# Sheet_1_3OLED.net
KiCad netlist of a schematic drawn in Altium Designer
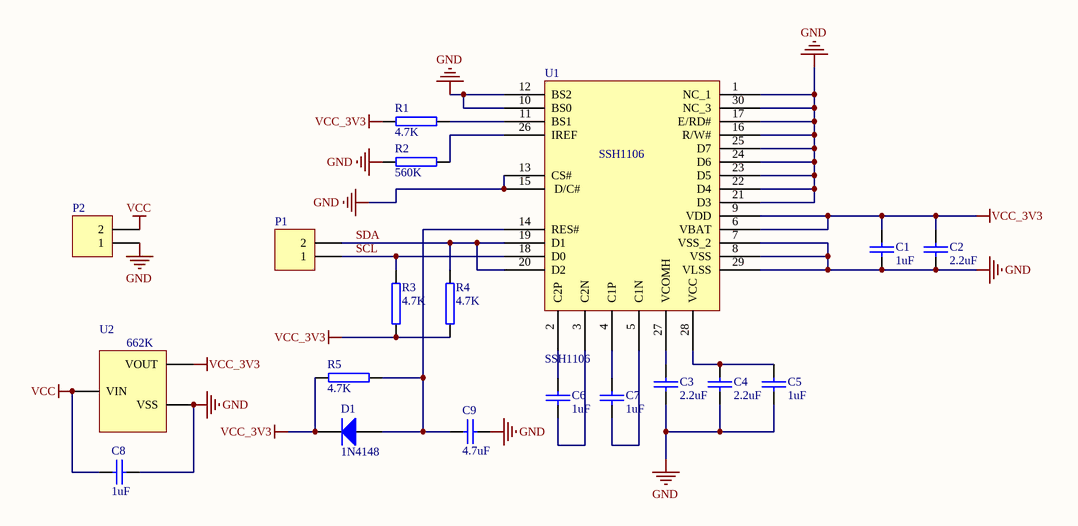
[diagram p0: Sheet_1.3OLED.SchDoc]

(export (version "E")
  (design (tool "Eeschema 10.0.6"))
  (components
    (comp (ref "C1")
      (value "1uF")
      (footprint "C0603")
      (description "贴片电容")
      (libsource (lib "Schlib_OLEDMCU") (part "C0603"))
    )
    (comp (ref "C2")
      (value "2.2uF")
      (footprint "C0603")
      (description "贴片电容")
      (libsource (lib "Schlib_OLEDMCU") (part "C0603"))
    )
    (comp (ref "C3")
      (value "2.2uF")
      (footprint "C0603")
      (description "贴片电容")
      (libsource (lib "Schlib_OLEDMCU") (part "C0603"))
    )
    (comp (ref "C4")
      (value "2.2uF")
      (footprint "C0603")
      (description "贴片电容")
      (libsource (lib "Schlib_OLEDMCU") (part "C0603"))
    )
    (comp (ref "C5")
      (value "1uF")
      (footprint "C0603")
      (description "贴片电容")
      (libsource (lib "Schlib_OLEDMCU") (part "C0603"))
    )
    (comp (ref "C6")
      (value "1uF")
      (footprint "C0603")
      (description "贴片电容")
      (libsource (lib "Schlib_OLEDMCU") (part "C0603"))
    )
    (comp (ref "C7")
      (value "1uF")
      (footprint "C0603")
      (description "贴片电容")
      (libsource (lib "Schlib_OLEDMCU") (part "C0603"))
    )
    (comp (ref "C8")
      (value "1uF")
      (footprint "C0603")
      (description "贴片电容")
      (libsource (lib "Schlib_OLEDMCU") (part "C0603"))
    )
    (comp (ref "C9")
      (value "4.7uF")
      (footprint "C0603")
      (description "贴片电容")
      (libsource (lib "Schlib_OLEDMCU") (part "C0603"))
    )
    (comp (ref "D1")
      (value "1N4148")
      (footprint "1n4148")
      (description "二极管")
      (libsource (lib "Schlib_OLEDMCU") (part "1N4148"))
    )
    (comp (ref "P1")
      (value "Header 2")
      (footprint "HDR1X2")
      (description "Header, 2-Pin")
      (fields (field (name "PUBLISHER") "Altium Limited"))
      (libsource (lib "Miscellaneous Connectors") (part "Header 2"))
    )
    (comp (ref "P2")
      (value "Header 2")
      (footprint "HDR1X2")
      (description "Header, 2-Pin")
      (fields (field (name "PUBLISHER") "Altium Limited"))
      (libsource (lib "Miscellaneous Connectors") (part "Header 2"))
    )
    (comp (ref "R1")
      (value "4.7K")
      (footprint "R0603")
      (description "贴片电阻")
      (libsource (lib "Schlib_OLEDMCU") (part "R0603"))
    )
    (comp (ref "R2")
      (value "560K")
      (footprint "R0603")
      (description "贴片电阻")
      (libsource (lib "Schlib_OLEDMCU") (part "R0603"))
    )
    (comp (ref "R3")
      (value "4.7K")
      (footprint "R0603")
      (description "贴片电阻")
      (libsource (lib "Schlib_OLEDMCU") (part "R0603"))
    )
    (comp (ref "R4")
      (value "4.7K")
      (footprint "R0603")
      (description "贴片电阻")
      (libsource (lib "Schlib_OLEDMCU") (part "R0603"))
    )
    (comp (ref "R5")
      (value "4.7K")
      (footprint "R0603")
      (description "贴片电阻")
      (libsource (lib "Schlib_OLEDMCU") (part "R0603"))
    )
    (comp (ref "U1")
      (value "SSH1106")
      (footprint "SSH1106")
      (description "1.3寸OLED")
      (libsource (lib "Schlib_OLEDMCU") (part "SSH1106"))
    )
    (comp (ref "U2")
      (value "Power")
      (footprint "662k")
      (description "稳压芯片")
      (libsource (lib "Schlib_OLEDMCU") (part "662K"))
    )
  )
  (nets
    (net (code "1") (name "/SCL") (class "Default")
      (node (ref "P1") (pin "1") (pinfunction "1_1") (pintype "passive"))
      (node (ref "R3") (pin "2") (pinfunction "2_2") (pintype "passive"))
      (node (ref "U1") (pin "18") (pinfunction "D0_18") (pintype "passive"))
    )
    (net (code "2") (name "/SDA") (class "Default")
      (node (ref "P1") (pin "2") (pinfunction "2_2") (pintype "passive"))
      (node (ref "R4") (pin "2") (pinfunction "2_2") (pintype "passive"))
      (node (ref "U1") (pin "19") (pinfunction "D1_19") (pintype "passive"))
      (node (ref "U1") (pin "20") (pinfunction "D2_20") (pintype "passive"))
    )
    (net (code "3") (name "GND") (class "Default")
      (node (ref "C1") (pin "2") (pinfunction "2_2") (pintype "passive"))
      (node (ref "C2") (pin "2") (pinfunction "2_2") (pintype "passive"))
      (node (ref "C3") (pin "2") (pinfunction "2_2") (pintype "passive"))
      (node (ref "C4") (pin "2") (pinfunction "2_2") (pintype "passive"))
      (node (ref "C5") (pin "2") (pinfunction "2_2") (pintype "passive"))
      (node (ref "C8") (pin "2") (pinfunction "2_2") (pintype "passive"))
      (node (ref "C9") (pin "2") (pinfunction "2_2") (pintype "passive"))
      (node (ref "P2") (pin "1") (pinfunction "1_1") (pintype "passive"))
      (node (ref "R2") (pin "1") (pinfunction "1_1") (pintype "passive"))
      (node (ref "U1") (pin "1") (pinfunction "NC_1_1") (pintype "passive"))
      (node (ref "U1") (pin "10") (pinfunction "BS0_10") (pintype "passive"))
      (node (ref "U1") (pin "12") (pinfunction "BS2_12") (pintype "passive"))
      (node (ref "U1") (pin "13") (pinfunction "CS#_13") (pintype "passive"))
      (node (ref "U1") (pin "15") (pinfunction "D/C#_15") (pintype "passive"))
      (node (ref "U1") (pin "16") (pinfunction "R/W#_16") (pintype "passive"))
      (node (ref "U1") (pin "17") (pinfunction "E/RD#_17") (pintype "passive"))
      (node (ref "U1") (pin "21") (pinfunction "D3_21") (pintype "passive"))
      (node (ref "U1") (pin "22") (pinfunction "D4_22") (pintype "passive"))
      (node (ref "U1") (pin "23") (pinfunction "D5_23") (pintype "passive"))
      (node (ref "U1") (pin "24") (pinfunction "D6_24") (pintype "passive"))
      (node (ref "U1") (pin "25") (pinfunction "D7_25") (pintype "passive"))
      (node (ref "U1") (pin "29") (pinfunction "VLSS_29") (pintype "passive"))
      (node (ref "U1") (pin "30") (pinfunction "NC_3_30") (pintype "passive"))
      (node (ref "U1") (pin "7") (pinfunction "VSS_2_7") (pintype "passive"))
      (node (ref "U1") (pin "8") (pinfunction "VSS_8") (pintype "passive"))
      (node (ref "U2") (pin "1") (pinfunction "VSS_1") (pintype "passive"))
    )
    (net (code "4") (name "Net-(D1-A)") (class "Default")
      (node (ref "C9") (pin "1") (pinfunction "1_1") (pintype "passive"))
      (node (ref "D1") (pin "1") (pinfunction "A_1") (pintype "passive"))
      (node (ref "R5") (pin "2") (pinfunction "2_2") (pintype "passive"))
      (node (ref "U1") (pin "14") (pinfunction "RES#_14") (pintype "passive"))
    )
    (net (code "5") (name "Net-(U1-BS1)") (class "Default")
      (node (ref "R1") (pin "2") (pinfunction "2_2") (pintype "passive"))
      (node (ref "U1") (pin "11") (pinfunction "BS1_11") (pintype "passive"))
    )
    (net (code "6") (name "Net-(U1-C1N)") (class "Default")
      (node (ref "C7") (pin "2") (pinfunction "2_2") (pintype "passive"))
      (node (ref "U1") (pin "5") (pinfunction "C1N_5") (pintype "passive"))
    )
    (net (code "7") (name "Net-(U1-C1P)") (class "Default")
      (node (ref "C7") (pin "1") (pinfunction "1_1") (pintype "passive"))
      (node (ref "U1") (pin "4") (pinfunction "C1P_4") (pintype "passive"))
    )
    (net (code "8") (name "Net-(U1-C2N)") (class "Default")
      (node (ref "C6") (pin "2") (pinfunction "2_2") (pintype "passive"))
      (node (ref "U1") (pin "3") (pinfunction "C2N_3") (pintype "passive"))
    )
    (net (code "9") (name "Net-(U1-C2P)") (class "Default")
      (node (ref "C6") (pin "1") (pinfunction "1_1") (pintype "passive"))
      (node (ref "U1") (pin "2") (pinfunction "C2P_2") (pintype "passive"))
    )
    (net (code "10") (name "Net-(U1-IREF)") (class "Default")
      (node (ref "R2") (pin "2") (pinfunction "2_2") (pintype "passive"))
      (node (ref "U1") (pin "26") (pinfunction "IREF_26") (pintype "passive"))
    )
    (net (code "11") (name "Net-(U1-VCC)") (class "Default")
      (node (ref "C4") (pin "1") (pinfunction "1_1") (pintype "passive"))
      (node (ref "C5") (pin "1") (pinfunction "1_1") (pintype "passive"))
      (node (ref "U1") (pin "28") (pinfunction "VCC_28") (pintype "passive"))
    )
    (net (code "12") (name "Net-(U1-VCOMH)") (class "Default")
      (node (ref "C3") (pin "1") (pinfunction "1_1") (pintype "passive"))
      (node (ref "U1") (pin "27") (pinfunction "VCOMH_27") (pintype "passive"))
    )
    (net (code "13") (name "VCC") (class "Default")
      (node (ref "C8") (pin "1") (pinfunction "1_1") (pintype "passive"))
      (node (ref "P2") (pin "2") (pinfunction "2_2") (pintype "passive"))
      (node (ref "U2") (pin "3") (pinfunction "VIN_3") (pintype "passive"))
    )
    (net (code "14") (name "VCC_3V3") (class "Default")
      (node (ref "C1") (pin "1") (pinfunction "1_1") (pintype "passive"))
      (node (ref "C2") (pin "1") (pinfunction "1_1") (pintype "passive"))
      (node (ref "D1") (pin "2") (pinfunction "K_2") (pintype "passive"))
      (node (ref "R1") (pin "1") (pinfunction "1_1") (pintype "passive"))
      (node (ref "R3") (pin "1") (pinfunction "1_1") (pintype "passive"))
      (node (ref "R4") (pin "1") (pinfunction "1_1") (pintype "passive"))
      (node (ref "R5") (pin "1") (pinfunction "1_1") (pintype "passive"))
      (node (ref "U1") (pin "6") (pinfunction "VBAT_6") (pintype "passive"))
      (node (ref "U1") (pin "9") (pinfunction "VDD_9") (pintype "passive"))
      (node (ref "U2") (pin "2") (pinfunction "VOUT_2") (pintype "passive"))
    )
  )
)
